# SCH_SpaceDrums_easyeda.net
KiCad netlist of a schematic drawn in EasyEDA
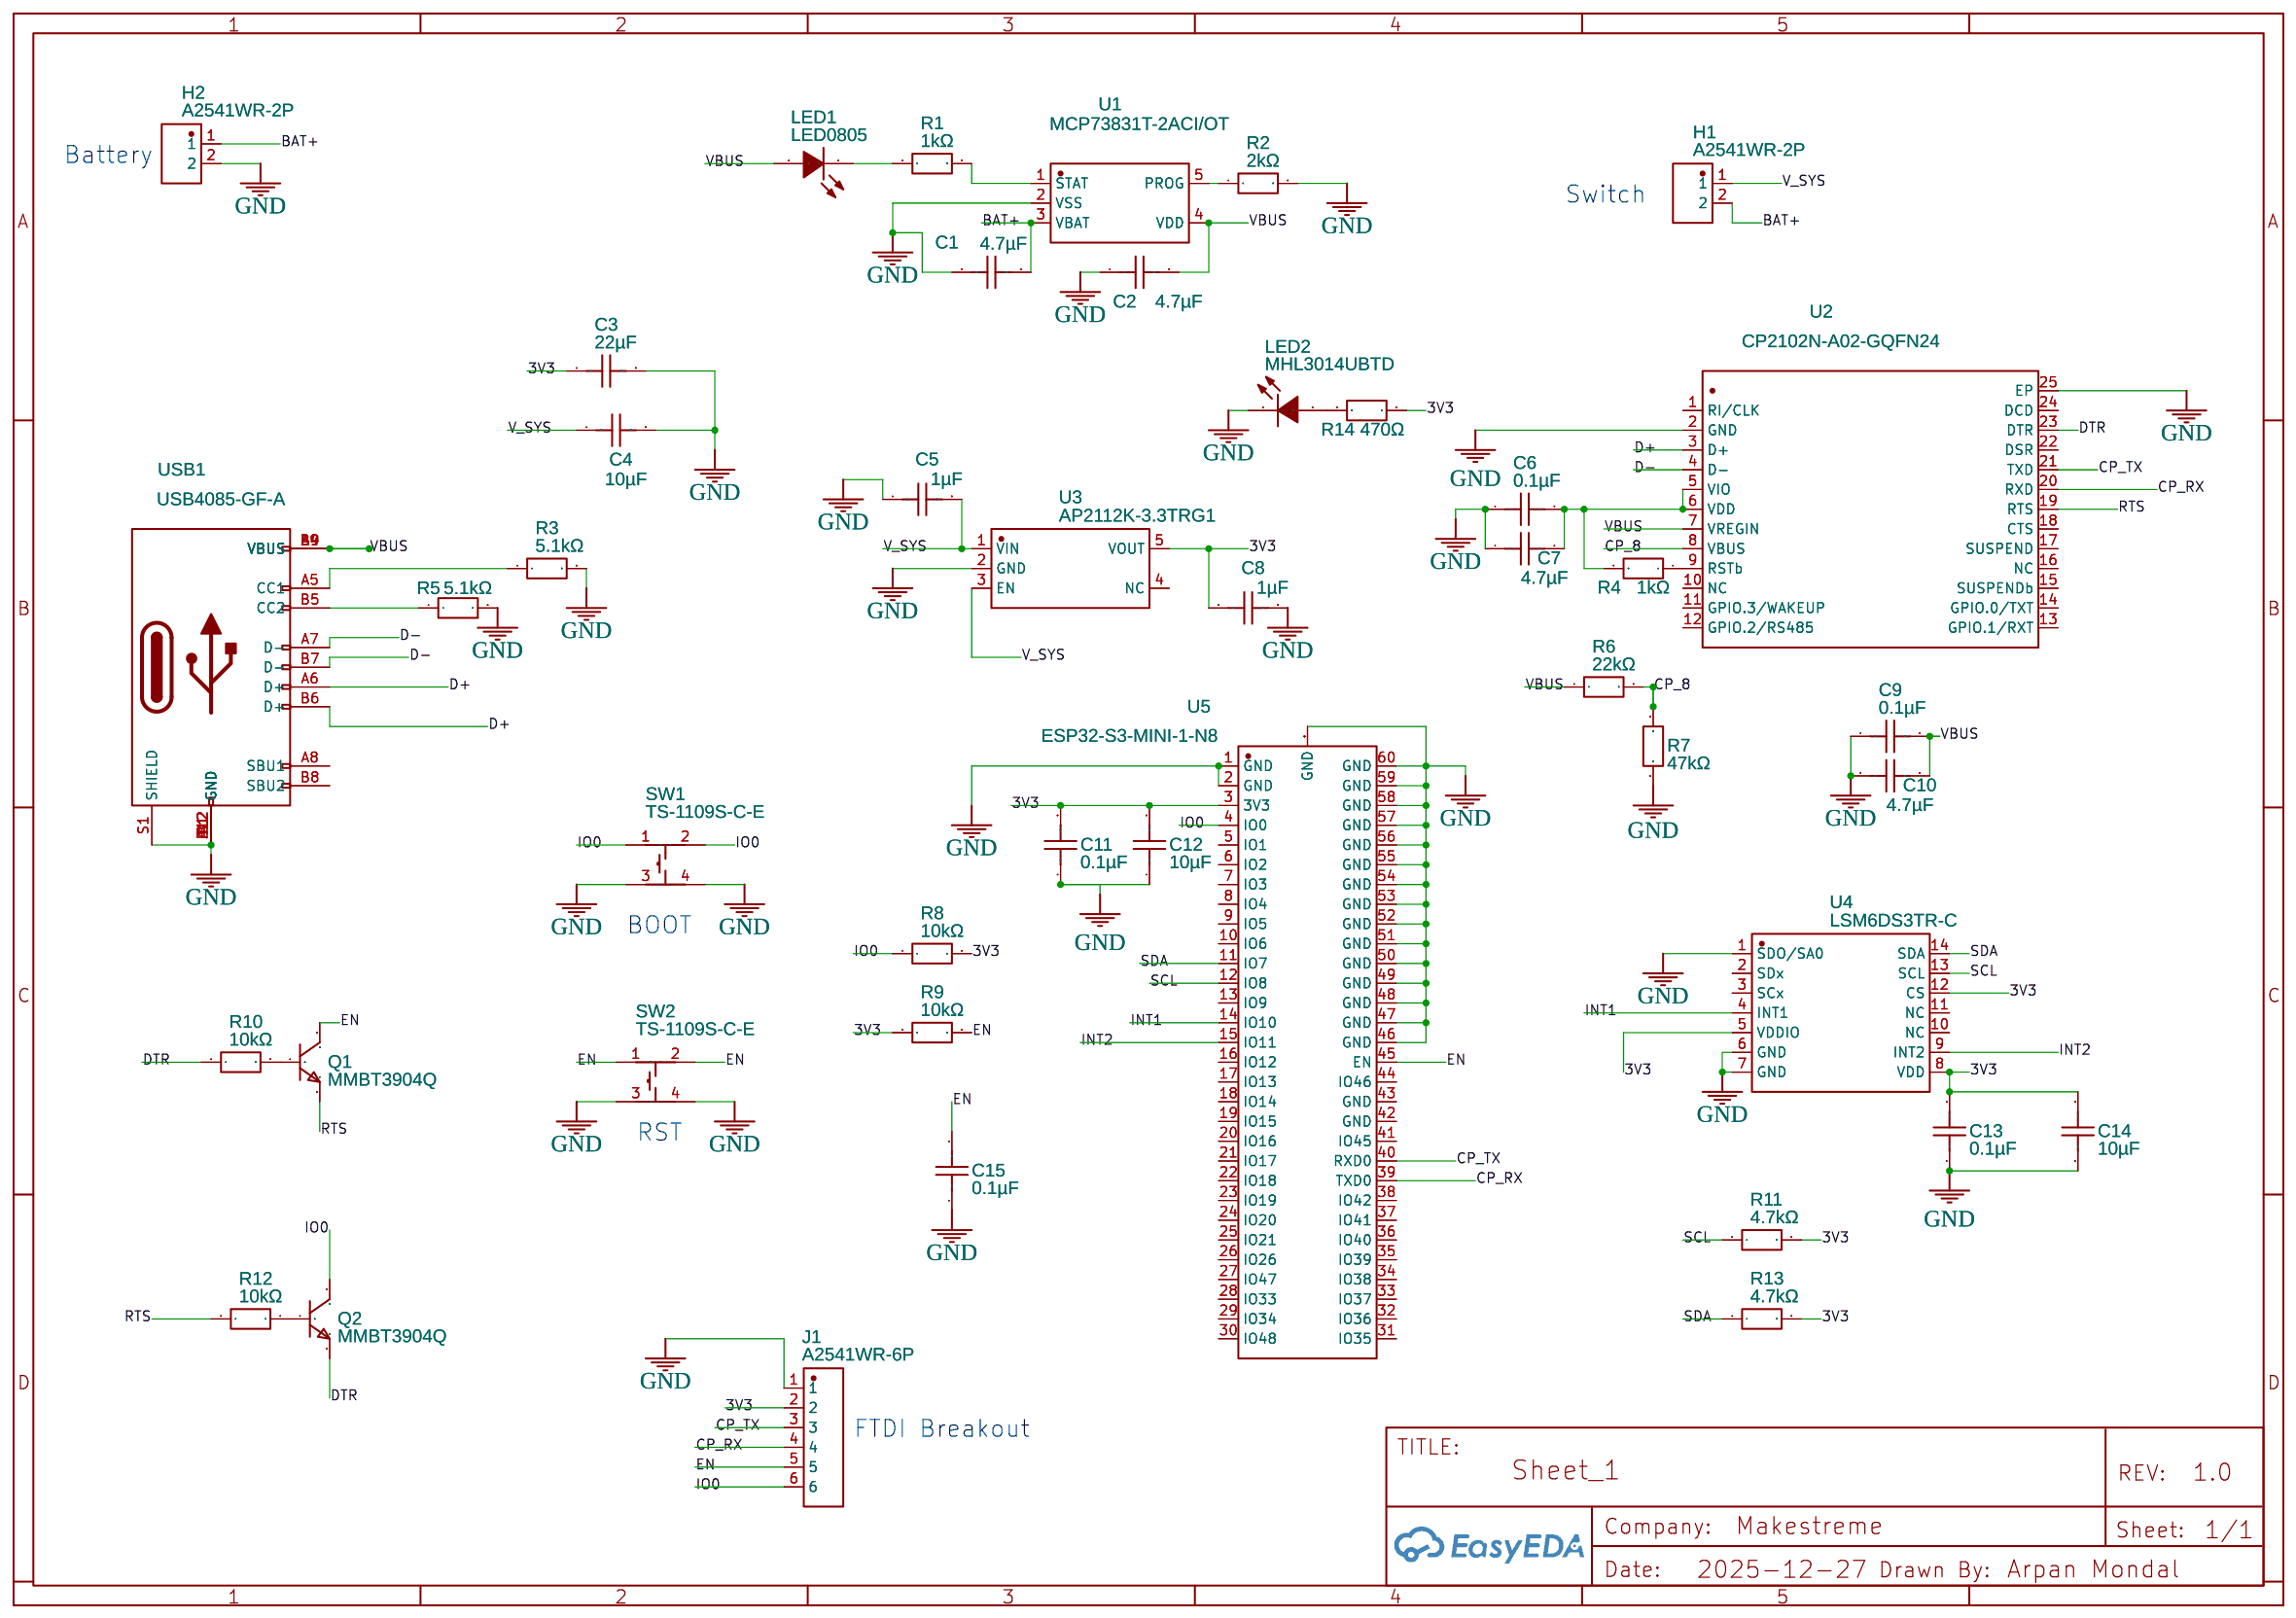
[diagram p0: schematic sheet]

(export (version "E")
  (design (tool "Eeschema 10.0.6"))
  (components
    (comp (ref "C1")
      (value "4.7µF")
      (fields
        (field (name "Manufacturer Part") "CC0805FRNPO0BN680")
        (field (name "Manufacturer") "YAGEO(国巨)")
      )
      (libsource (lib "") (part "CC0805FRNPO0BN680"))
    )
    (comp (ref "C2")
      (value "4.7µF")
      (fields
        (field (name "Manufacturer Part") "CC0805FRNPO0BN680")
        (field (name "Manufacturer") "YAGEO(国巨)")
      )
      (libsource (lib "") (part "CC0805FRNPO0BN680"))
    )
    (comp (ref "C3")
      (value "22µF")
      (fields
        (field (name "Manufacturer Part") "CC0805FRNPO0BN680")
        (field (name "Manufacturer") "YAGEO(国巨)")
      )
      (libsource (lib "") (part "CC0805FRNPO0BN680"))
    )
    (comp (ref "C4")
      (value "10µF")
      (fields
        (field (name "Manufacturer Part") "CC0805FRNPO0BN680")
        (field (name "Manufacturer") "YAGEO(国巨)")
      )
      (libsource (lib "") (part "CC0805FRNPO0BN680"))
    )
    (comp (ref "C5")
      (value "1µF")
      (fields
        (field (name "Manufacturer Part") "CC0805FRNPO0BN680")
        (field (name "Manufacturer") "YAGEO(国巨)")
      )
      (libsource (lib "") (part "CC0805FRNPO0BN680"))
    )
    (comp (ref "C6")
      (value "0.1µF")
      (fields
        (field (name "Manufacturer Part") "CC0805FRNPO0BN680")
        (field (name "Manufacturer") "YAGEO(国巨)")
      )
      (libsource (lib "") (part "CC0805FRNPO0BN680"))
    )
    (comp (ref "C7")
      (value "4.7µF")
      (fields
        (field (name "Manufacturer Part") "CC0805FRNPO0BN680")
        (field (name "Manufacturer") "YAGEO(国巨)")
      )
      (libsource (lib "") (part "CC0805FRNPO0BN680"))
    )
    (comp (ref "C8")
      (value "1µF")
      (fields
        (field (name "Manufacturer Part") "CC0805FRNPO0BN680")
        (field (name "Manufacturer") "YAGEO(国巨)")
      )
      (libsource (lib "") (part "CC0805FRNPO0BN680"))
    )
    (comp (ref "C9")
      (value "0.1µF")
      (fields
        (field (name "Manufacturer Part") "CC0805FRNPO0BN680")
        (field (name "Manufacturer") "YAGEO(国巨)")
      )
      (libsource (lib "") (part "CC0805FRNPO0BN680"))
    )
    (comp (ref "C10")
      (value "4.7µF")
      (fields
        (field (name "Manufacturer Part") "CC0805FRNPO0BN680")
        (field (name "Manufacturer") "YAGEO(国巨)")
      )
      (libsource (lib "") (part "CC0805FRNPO0BN680"))
    )
    (comp (ref "C11")
      (value "0.1µF")
      (fields
        (field (name "Manufacturer Part") "CC0805FRNPO0BN680")
        (field (name "Manufacturer") "YAGEO(国巨)")
      )
      (libsource (lib "") (part "CC0805FRNPO0BN680_1"))
    )
    (comp (ref "C12")
      (value "10µF")
      (fields
        (field (name "Manufacturer Part") "CC0805FRNPO0BN680")
        (field (name "Manufacturer") "YAGEO(国巨)")
      )
      (libsource (lib "") (part "CC0805FRNPO0BN680_1"))
    )
    (comp (ref "C13")
      (value "0.1µF")
      (fields
        (field (name "Manufacturer Part") "CC0805FRNPO0BN680")
        (field (name "Manufacturer") "YAGEO(国巨)")
      )
      (libsource (lib "") (part "CC0805FRNPO0BN680_1"))
    )
    (comp (ref "C14")
      (value "10µF")
      (fields
        (field (name "Manufacturer Part") "CC0805FRNPO0BN680")
        (field (name "Manufacturer") "YAGEO(国巨)")
      )
      (libsource (lib "") (part "CC0805FRNPO0BN680_1"))
    )
    (comp (ref "C15")
      (value "0.1µF")
      (fields
        (field (name "Manufacturer Part") "CC0805FRNPO0BN680")
        (field (name "Manufacturer") "YAGEO(国巨)")
      )
      (libsource (lib "") (part "CC0805FRNPO0BN680_1"))
    )
    (comp (ref "H1")
      (value "A2541WR-2P")
      (fields (field (name "Manufacturer") "CJT(长江连接器)"))
      (libsource (lib "") (part "A2541WR-2P"))
    )
    (comp (ref "H2")
      (value "A2541WR-2P")
      (fields (field (name "Manufacturer") "CJT(长江连接器)"))
      (libsource (lib "") (part "A2541WR-2P"))
    )
    (comp (ref "J1")
      (value "A2541WR-6P")
      (fields (field (name "Manufacturer") "CJT(长江连接器)"))
      (libsource (lib "") (part "A2541WR-6P"))
    )
    (comp (ref "LED1")
      (value "LED0805")
      (fields (field (name "Manufacturer Part") "led0805"))
      (libsource (lib "") (part "LED0805"))
    )
    (comp (ref "LED2")
      (value "MHL3014UBTD")
      (fields (field (name "Manufacturer") "MEIHUA(美华)"))
      (libsource (lib "") (part "MHL3014UBTD"))
    )
    (comp (ref "Q1")
      (value "MMBT3904Q")
      (fields (field (name "Manufacturer") "YANGJIE(扬杰)"))
      (libsource (lib "") (part "MMBT3904Q"))
    )
    (comp (ref "Q2")
      (value "MMBT3904Q")
      (fields (field (name "Manufacturer") "YANGJIE(扬杰)"))
      (libsource (lib "") (part "MMBT3904Q"))
    )
    (comp (ref "R1")
      (value "1kΩ")
      (fields (field (name "Manufacturer Part") "FRC0805F7873TS") (field (name "Manufacturer") "FOJAN(富捷)"))
      (libsource (lib "") (part "FRC0805F7873TS"))
    )
    (comp (ref "R2")
      (value "2kΩ")
      (fields (field (name "Manufacturer Part") "FRC0805F7873TS") (field (name "Manufacturer") "FOJAN(富捷)"))
      (libsource (lib "") (part "FRC0805F7873TS"))
    )
    (comp (ref "R3")
      (value "5.1kΩ")
      (fields (field (name "Manufacturer Part") "FRC0805F7873TS") (field (name "Manufacturer") "FOJAN(富捷)"))
      (libsource (lib "") (part "FRC0805F7873TS"))
    )
    (comp (ref "R4")
      (value "1kΩ")
      (fields (field (name "Manufacturer Part") "FRC0805F7873TS") (field (name "Manufacturer") "FOJAN(富捷)"))
      (libsource (lib "") (part "FRC0805F7873TS_1"))
    )
    (comp (ref "R5")
      (value "5.1kΩ")
      (fields (field (name "Manufacturer Part") "FRC0805F7873TS") (field (name "Manufacturer") "FOJAN(富捷)"))
      (libsource (lib "") (part "FRC0805F7873TS"))
    )
    (comp (ref "R6")
      (value "22kΩ")
      (fields (field (name "Manufacturer Part") "FRC0805F7873TS") (field (name "Manufacturer") "FOJAN(富捷)"))
      (libsource (lib "") (part "FRC0805F7873TS"))
    )
    (comp (ref "R7")
      (value "47kΩ")
      (fields (field (name "Manufacturer Part") "FRC0805F7873TS") (field (name "Manufacturer") "FOJAN(富捷)"))
      (libsource (lib "") (part "FRC0805F7873TS_2"))
    )
    (comp (ref "R8")
      (value "10kΩ")
      (fields (field (name "Manufacturer Part") "FRC0805F7873TS") (field (name "Manufacturer") "FOJAN(富捷)"))
      (libsource (lib "") (part "FRC0805F7873TS"))
    )
    (comp (ref "R9")
      (value "10kΩ")
      (fields (field (name "Manufacturer Part") "FRC0805F7873TS") (field (name "Manufacturer") "FOJAN(富捷)"))
      (libsource (lib "") (part "FRC0805F7873TS"))
    )
    (comp (ref "R10")
      (value "10kΩ")
      (fields (field (name "Manufacturer Part") "FRC0805F7873TS") (field (name "Manufacturer") "FOJAN(富捷)"))
      (libsource (lib "") (part "FRC0805F7873TS"))
    )
    (comp (ref "R11")
      (value "4.7kΩ")
      (fields (field (name "Manufacturer Part") "FRC0805F7873TS") (field (name "Manufacturer") "FOJAN(富捷)"))
      (libsource (lib "") (part "FRC0805F7873TS"))
    )
    (comp (ref "R12")
      (value "10kΩ")
      (fields (field (name "Manufacturer Part") "FRC0805F7873TS") (field (name "Manufacturer") "FOJAN(富捷)"))
      (libsource (lib "") (part "FRC0805F7873TS_1"))
    )
    (comp (ref "R13")
      (value "4.7kΩ")
      (fields (field (name "Manufacturer Part") "FRC0805F7873TS") (field (name "Manufacturer") "FOJAN(富捷)"))
      (libsource (lib "") (part "FRC0805F7873TS"))
    )
    (comp (ref "R14")
      (value "470Ω")
      (fields (field (name "Manufacturer Part") "FRC0805F7873TS") (field (name "Manufacturer") "FOJAN(富捷)"))
      (libsource (lib "") (part "FRC0805F7873TS_1"))
    )
    (comp (ref "SW1")
      (value "TS-1109S-C-E")
      (fields (field (name "Manufacturer") "XKB Connectivity(中国星坤)"))
      (libsource (lib "") (part "TS-1109S-C-E"))
    )
    (comp (ref "SW2")
      (value "TS-1109S-C-E")
      (fields (field (name "Manufacturer") "XKB Connectivity(中国星坤)"))
      (libsource (lib "") (part "TS-1109S-C-E"))
    )
    (comp (ref "U1")
      (value "MCP73831T-2ACI/OT")
      (fields (field (name "Manufacturer") "MICROCHIP(美国微芯)"))
      (libsource (lib "") (part "MCP73831T-2ACI/OT"))
    )
    (comp (ref "U2")
      (value "CP2102N-A02-GQFN24")
      (fields (field (name "Manufacturer") "SKYWORKS/SILICON LABS(芯科)"))
      (libsource (lib "") (part "CP2102N-A02-GQFN24"))
    )
    (comp (ref "U3")
      (value "AP2112K-3.3TRG1")
      (fields (field (name "Manufacturer") "DIODES(美台)"))
      (libsource (lib "") (part "AP2112K-3.3TRG1"))
    )
    (comp (ref "U4")
      (value "LSM6DS3TR-C")
      (fields (field (name "Manufacturer") "ST(意法半导体)"))
      (libsource (lib "") (part "LSM6DS3TR-C"))
    )
    (comp (ref "U5")
      (value "ESP32-S3-MINI-1-N8")
      (fields (field (name "Manufacturer") "ESPRESSIF(乐鑫)"))
      (libsource (lib "") (part "ESP32-S3-MINI-1-N8"))
    )
    (comp (ref "USB1") (value "USB4085-GF-A") (libsource (lib "") (part "USB4085-GF-A")))
  )
  (nets
    (net (code "1") (name "/3V3") (class "Default")
      (node (ref "C11") (pin "2") (pinfunction "2_2") (pintype "unspecified"))
      (node (ref "C12") (pin "2") (pinfunction "2_2") (pintype "unspecified"))
      (node (ref "C13") (pin "2") (pinfunction "2_2") (pintype "unspecified"))
      (node (ref "C14") (pin "2") (pinfunction "2_2") (pintype "unspecified"))
      (node (ref "C3") (pin "1") (pinfunction "1_1") (pintype "unspecified"))
      (node (ref "C8") (pin "1") (pinfunction "1_1") (pintype "unspecified"))
      (node (ref "J1") (pin "2") (pinfunction "2_2") (pintype "unspecified"))
      (node (ref "R11") (pin "2") (pinfunction "2_2") (pintype "unspecified"))
      (node (ref "R13") (pin "2") (pinfunction "2_2") (pintype "unspecified"))
      (node (ref "R14") (pin "1") (pinfunction "1_1") (pintype "unspecified"))
      (node (ref "R8") (pin "2") (pinfunction "2_2") (pintype "unspecified"))
      (node (ref "R9") (pin "1") (pinfunction "1_1") (pintype "unspecified"))
      (node (ref "U3") (pin "5") (pinfunction "VOUT_5") (pintype "unspecified"))
      (node (ref "U4") (pin "12") (pinfunction "CS_12") (pintype "unspecified"))
      (node (ref "U4") (pin "5") (pinfunction "VDDIO_5") (pintype "unspecified"))
      (node (ref "U4") (pin "8") (pinfunction "VDD_8") (pintype "unspecified"))
      (node (ref "U5") (pin "3") (pinfunction "3V3_3") (pintype "unspecified"))
    )
    (net (code "2") (name "/BAT+") (class "Default")
      (node (ref "C1") (pin "2") (pinfunction "2_2") (pintype "unspecified"))
      (node (ref "H1") (pin "2") (pinfunction "2_2") (pintype "unspecified"))
      (node (ref "H2") (pin "1") (pinfunction "1_1") (pintype "unspecified"))
      (node (ref "U1") (pin "3") (pinfunction "VBAT_3") (pintype "unspecified"))
    )
    (net (code "3") (name "/CP_8") (class "Default")
      (node (ref "R6") (pin "2") (pinfunction "2_2") (pintype "unspecified"))
      (node (ref "R7") (pin "2") (pinfunction "2_2") (pintype "unspecified"))
      (node (ref "U2") (pin "8") (pinfunction "VBUS_8") (pintype "unspecified"))
    )
    (net (code "4") (name "/CP_RX") (class "Default")
      (node (ref "J1") (pin "4") (pinfunction "4_4") (pintype "unspecified"))
      (node (ref "U2") (pin "20") (pinfunction "RXD_20") (pintype "unspecified"))
      (node (ref "U5") (pin "39") (pinfunction "TXD0_39") (pintype "unspecified"))
    )
    (net (code "5") (name "/CP_TX") (class "Default")
      (node (ref "J1") (pin "3") (pinfunction "3_3") (pintype "unspecified"))
      (node (ref "U2") (pin "21") (pinfunction "TXD_21") (pintype "unspecified"))
      (node (ref "U5") (pin "40") (pinfunction "RXD0_40") (pintype "unspecified"))
    )
    (net (code "6") (name "/D+") (class "Default")
      (node (ref "U2") (pin "3") (pinfunction "D+_3") (pintype "unspecified"))
      (node (ref "USB1") (pin "A6") (pinfunction "D+_A6") (pintype "bidirectional"))
      (node (ref "USB1") (pin "B6") (pinfunction "D+_B6") (pintype "bidirectional"))
    )
    (net (code "7") (name "/D-") (class "Default")
      (node (ref "U2") (pin "4") (pinfunction "D-_4") (pintype "unspecified"))
      (node (ref "USB1") (pin "A7") (pinfunction "D-_A7") (pintype "bidirectional"))
      (node (ref "USB1") (pin "B7") (pinfunction "D-_B7") (pintype "bidirectional"))
    )
    (net (code "8") (name "/DTR") (class "Default")
      (node (ref "Q2") (pin "2") (pinfunction "E_2") (pintype "unspecified"))
      (node (ref "R10") (pin "1") (pinfunction "1_1") (pintype "unspecified"))
      (node (ref "U2") (pin "23") (pinfunction "DTR_23") (pintype "unspecified"))
    )
    (net (code "9") (name "/EN") (class "Default")
      (node (ref "C15") (pin "2") (pinfunction "2_2") (pintype "unspecified"))
      (node (ref "J1") (pin "5") (pinfunction "5_5") (pintype "unspecified"))
      (node (ref "Q1") (pin "3") (pinfunction "C_3") (pintype "unspecified"))
      (node (ref "R9") (pin "2") (pinfunction "2_2") (pintype "unspecified"))
      (node (ref "SW2") (pin "1") (pinfunction "1_1") (pintype "unspecified"))
      (node (ref "SW2") (pin "2") (pinfunction "2_2") (pintype "unspecified"))
      (node (ref "U5") (pin "45") (pinfunction "EN_45") (pintype "unspecified"))
    )
    (net (code "10") (name "/INT1") (class "Default")
      (node (ref "U4") (pin "4") (pinfunction "INT1_4") (pintype "unspecified"))
      (node (ref "U5") (pin "14") (pinfunction "IO10_14") (pintype "unspecified"))
    )
    (net (code "11") (name "/INT2") (class "Default")
      (node (ref "U4") (pin "9") (pinfunction "INT2_9") (pintype "unspecified"))
      (node (ref "U5") (pin "15") (pinfunction "IO11_15") (pintype "unspecified"))
    )
    (net (code "12") (name "/IO0") (class "Default")
      (node (ref "J1") (pin "6") (pinfunction "6_6") (pintype "unspecified"))
      (node (ref "Q2") (pin "3") (pinfunction "C_3") (pintype "unspecified"))
      (node (ref "R8") (pin "1") (pinfunction "1_1") (pintype "unspecified"))
      (node (ref "SW1") (pin "1") (pinfunction "1_1") (pintype "unspecified"))
      (node (ref "SW1") (pin "2") (pinfunction "2_2") (pintype "unspecified"))
      (node (ref "U5") (pin "4") (pinfunction "IO0_4") (pintype "unspecified"))
    )
    (net (code "13") (name "/RTS") (class "Default")
      (node (ref "Q1") (pin "2") (pinfunction "E_2") (pintype "unspecified"))
      (node (ref "R12") (pin "2") (pinfunction "2_2") (pintype "unspecified"))
      (node (ref "U2") (pin "19") (pinfunction "RTS_19") (pintype "unspecified"))
    )
    (net (code "14") (name "/SCL") (class "Default")
      (node (ref "R11") (pin "1") (pinfunction "1_1") (pintype "unspecified"))
      (node (ref "U4") (pin "13") (pinfunction "SCL_13") (pintype "unspecified"))
      (node (ref "U5") (pin "12") (pinfunction "IO8_12") (pintype "unspecified"))
    )
    (net (code "15") (name "/SDA") (class "Default")
      (node (ref "R13") (pin "1") (pinfunction "1_1") (pintype "unspecified"))
      (node (ref "U4") (pin "14") (pinfunction "SDA_14") (pintype "unspecified"))
      (node (ref "U5") (pin "11") (pinfunction "IO7_11") (pintype "unspecified"))
    )
    (net (code "16") (name "/VBUS") (class "Default")
      (node (ref "C10") (pin "2") (pinfunction "2_2") (pintype "unspecified"))
      (node (ref "C2") (pin "2") (pinfunction "2_2") (pintype "unspecified"))
      (node (ref "C9") (pin "2") (pinfunction "2_2") (pintype "unspecified"))
      (node (ref "LED1") (pin "2") (pinfunction "+_2") (pintype "unspecified"))
      (node (ref "R6") (pin "1") (pinfunction "1_1") (pintype "unspecified"))
      (node (ref "U1") (pin "4") (pinfunction "VDD_4") (pintype "unspecified"))
      (node (ref "U2") (pin "7") (pinfunction "VREGIN_7") (pintype "unspecified"))
      (node (ref "USB1") (pin "A4") (pinfunction "VBUS_A4") (pintype "bidirectional"))
      (node (ref "USB1") (pin "A9") (pinfunction "VBUS_A9") (pintype "unspecified"))
      (node (ref "USB1") (pin "B4") (pinfunction "VBUS_B4") (pintype "unspecified"))
      (node (ref "USB1") (pin "B9") (pinfunction "VBUS_B9") (pintype "unspecified"))
    )
    (net (code "17") (name "/V_SYS") (class "Default")
      (node (ref "C4") (pin "1") (pinfunction "1_1") (pintype "unspecified"))
      (node (ref "C5") (pin "2") (pinfunction "2_2") (pintype "unspecified"))
      (node (ref "H1") (pin "1") (pinfunction "1_1") (pintype "unspecified"))
      (node (ref "U3") (pin "1") (pinfunction "VIN_1") (pintype "unspecified"))
      (node (ref "U3") (pin "3") (pinfunction "EN_3") (pintype "unspecified"))
    )
    (net (code "18") (name "GND") (class "Default")
      (node (ref "C1") (pin "1") (pinfunction "1_1") (pintype "unspecified"))
      (node (ref "C10") (pin "1") (pinfunction "1_1") (pintype "unspecified"))
      (node (ref "C11") (pin "1") (pinfunction "1_1") (pintype "unspecified"))
      (node (ref "C12") (pin "1") (pinfunction "1_1") (pintype "unspecified"))
      (node (ref "C13") (pin "1") (pinfunction "1_1") (pintype "unspecified"))
      (node (ref "C14") (pin "1") (pinfunction "1_1") (pintype "unspecified"))
      (node (ref "C15") (pin "1") (pinfunction "1_1") (pintype "unspecified"))
      (node (ref "C2") (pin "1") (pinfunction "1_1") (pintype "unspecified"))
      (node (ref "C3") (pin "2") (pinfunction "2_2") (pintype "unspecified"))
      (node (ref "C4") (pin "2") (pinfunction "2_2") (pintype "unspecified"))
      (node (ref "C5") (pin "1") (pinfunction "1_1") (pintype "unspecified"))
      (node (ref "C6") (pin "1") (pinfunction "1_1") (pintype "unspecified"))
      (node (ref "C7") (pin "1") (pinfunction "1_1") (pintype "unspecified"))
      (node (ref "C8") (pin "2") (pinfunction "2_2") (pintype "unspecified"))
      (node (ref "C9") (pin "1") (pinfunction "1_1") (pintype "unspecified"))
      (node (ref "H2") (pin "2") (pinfunction "2_2") (pintype "unspecified"))
      (node (ref "J1") (pin "1") (pinfunction "1_1") (pintype "unspecified"))
      (node (ref "LED2") (pin "1") (pinfunction "-_1") (pintype "unspecified"))
      (node (ref "R2") (pin "2") (pinfunction "2_2") (pintype "unspecified"))
      (node (ref "R3") (pin "2") (pinfunction "2_2") (pintype "unspecified"))
      (node (ref "R5") (pin "2") (pinfunction "2_2") (pintype "unspecified"))
      (node (ref "R7") (pin "1") (pinfunction "1_1") (pintype "unspecified"))
      (node (ref "SW1") (pin "3") (pinfunction "3_3") (pintype "unspecified"))
      (node (ref "SW1") (pin "4") (pinfunction "4_4") (pintype "unspecified"))
      (node (ref "SW2") (pin "3") (pinfunction "3_3") (pintype "unspecified"))
      (node (ref "SW2") (pin "4") (pinfunction "4_4") (pintype "unspecified"))
      (node (ref "U1") (pin "2") (pinfunction "VSS_2") (pintype "unspecified"))
      (node (ref "U2") (pin "2") (pinfunction "GND_2") (pintype "unspecified"))
      (node (ref "U2") (pin "25") (pinfunction "EP_25") (pintype "unspecified"))
      (node (ref "U3") (pin "2") (pinfunction "GND_2") (pintype "unspecified"))
      (node (ref "U4") (pin "1") (pinfunction "SDO/SA0_1") (pintype "unspecified"))
      (node (ref "U4") (pin "6") (pinfunction "GND_6") (pintype "unspecified"))
      (node (ref "U4") (pin "7") (pinfunction "GND_7") (pintype "unspecified"))
      (node (ref "U5") (pin "1") (pinfunction "GND_1") (pintype "unspecified"))
      (node (ref "U5") (pin "2") (pinfunction "GND_2") (pintype "unspecified"))
      (node (ref "U5") (pin "46") (pinfunction "GND_46") (pintype "unspecified"))
      (node (ref "U5") (pin "47") (pinfunction "GND_47") (pintype "unspecified"))
      (node (ref "U5") (pin "48") (pinfunction "GND_48") (pintype "unspecified"))
      (node (ref "U5") (pin "49") (pinfunction "GND_49") (pintype "unspecified"))
      (node (ref "U5") (pin "50") (pinfunction "GND_50") (pintype "unspecified"))
      (node (ref "U5") (pin "51") (pinfunction "GND_51") (pintype "unspecified"))
      (node (ref "U5") (pin "52") (pinfunction "GND_52") (pintype "unspecified"))
      (node (ref "U5") (pin "53") (pinfunction "GND_53") (pintype "unspecified"))
      (node (ref "U5") (pin "54") (pinfunction "GND_54") (pintype "unspecified"))
      (node (ref "U5") (pin "55") (pinfunction "GND_55") (pintype "unspecified"))
      (node (ref "U5") (pin "56") (pinfunction "GND_56") (pintype "unspecified"))
      (node (ref "U5") (pin "57") (pinfunction "GND_57") (pintype "unspecified"))
      (node (ref "U5") (pin "58") (pinfunction "GND_58") (pintype "unspecified"))
      (node (ref "U5") (pin "59") (pinfunction "GND_59") (pintype "unspecified"))
      (node (ref "U5") (pin "60") (pinfunction "GND_60") (pintype "unspecified"))
      (node (ref "U5") (pin "GND") (pinfunction "GND_GND") (pintype "unspecified"))
      (node (ref "USB1") (pin "A1") (pinfunction "GND_A1") (pintype "bidirectional"))
      (node (ref "USB1") (pin "A12") (pinfunction "GND_A12") (pintype "unspecified"))
      (node (ref "USB1") (pin "B1") (pinfunction "GND_B1") (pintype "unspecified"))
      (node (ref "USB1") (pin "B12") (pinfunction "GND_B12") (pintype "unspecified"))
      (node (ref "USB1") (pin "S1") (pinfunction "SHIELD_S1") (pintype "unspecified"))
    )
    (net (code "19") (name "Net-(LED1--)") (class "Default")
      (node (ref "LED1") (pin "1") (pinfunction "-_1") (pintype "unspecified"))
      (node (ref "R1") (pin "1") (pinfunction "1_1") (pintype "unspecified"))
    )
    (net (code "20") (name "Net-(LED2-+)") (class "Default")
      (node (ref "LED2") (pin "2") (pinfunction "+_2") (pintype "unspecified"))
      (node (ref "R14") (pin "2") (pinfunction "2_2") (pintype "unspecified"))
    )
    (net (code "21") (name "Net-(Q1-B)") (class "Default")
      (node (ref "Q1") (pin "1") (pinfunction "B_1") (pintype "unspecified"))
      (node (ref "R10") (pin "2") (pinfunction "2_2") (pintype "unspecified"))
    )
    (net (code "22") (name "Net-(Q2-B)") (class "Default")
      (node (ref "Q2") (pin "1") (pinfunction "B_1") (pintype "unspecified"))
      (node (ref "R12") (pin "1") (pinfunction "1_1") (pintype "unspecified"))
    )
    (net (code "23") (name "Net-(U1-PROG)") (class "Default")
      (node (ref "R2") (pin "1") (pinfunction "1_1") (pintype "unspecified"))
      (node (ref "U1") (pin "5") (pinfunction "PROG_5") (pintype "unspecified"))
    )
    (net (code "24") (name "Net-(U1-STAT)") (class "Default")
      (node (ref "R1") (pin "2") (pinfunction "2_2") (pintype "unspecified"))
      (node (ref "U1") (pin "1") (pinfunction "STAT_1") (pintype "unspecified"))
    )
    (net (code "25") (name "Net-(U2-RSTb)") (class "Default")
      (node (ref "R4") (pin "1") (pinfunction "1_1") (pintype "unspecified"))
      (node (ref "U2") (pin "9") (pinfunction "RSTb_9") (pintype "unspecified"))
    )
    (net (code "26") (name "Net-(U2-VDD)") (class "Default")
      (node (ref "C6") (pin "2") (pinfunction "2_2") (pintype "unspecified"))
      (node (ref "C7") (pin "2") (pinfunction "2_2") (pintype "unspecified"))
      (node (ref "R4") (pin "2") (pinfunction "2_2") (pintype "unspecified"))
      (node (ref "U2") (pin "5") (pinfunction "VIO_5") (pintype "unspecified"))
      (node (ref "U2") (pin "6") (pinfunction "VDD_6") (pintype "unspecified"))
    )
    (net (code "27") (name "Net-(USB1-CC1)") (class "Default")
      (node (ref "R3") (pin "1") (pinfunction "1_1") (pintype "unspecified"))
      (node (ref "USB1") (pin "A5") (pinfunction "CC1_A5") (pintype "bidirectional"))
    )
    (net (code "28") (name "Net-(USB1-CC2)") (class "Default")
      (node (ref "R5") (pin "1") (pinfunction "1_1") (pintype "unspecified"))
      (node (ref "USB1") (pin "B5") (pinfunction "CC2_B5") (pintype "bidirectional"))
    )
    (net (code "29") (name "unconnected-(U2-CTS-Pad18)") (class "Default")
      (node (ref "U2") (pin "18") (pinfunction "CTS_18") (pintype "unspecified"))
    )
    (net (code "30") (name "unconnected-(U2-DCD-Pad24)") (class "Default")
      (node (ref "U2") (pin "24") (pinfunction "DCD_24") (pintype "unspecified"))
    )
    (net (code "31") (name "unconnected-(U2-DSR-Pad22)") (class "Default")
      (node (ref "U2") (pin "22") (pinfunction "DSR_22") (pintype "unspecified"))
    )
    (net (code "32") (name "unconnected-(U2-GPIO.0{slash}TXT-Pad14)") (class "Default")
      (node (ref "U2") (pin "14") (pinfunction "GPIO.0/TXT_14") (pintype "unspecified"))
    )
    (net (code "33") (name "unconnected-(U2-GPIO.1{slash}RXT-Pad13)") (class "Default")
      (node (ref "U2") (pin "13") (pinfunction "GPIO.1/RXT_13") (pintype "unspecified"))
    )
    (net (code "34") (name "unconnected-(U2-GPIO.2{slash}RS485-Pad12)") (class "Default")
      (node (ref "U2") (pin "12") (pinfunction "GPIO.2/RS485_12") (pintype "unspecified"))
    )
    (net (code "35") (name "unconnected-(U2-GPIO.3{slash}WAKEUP-Pad11)") (class "Default")
      (node (ref "U2") (pin "11") (pinfunction "GPIO.3/WAKEUP_11") (pintype "unspecified"))
    )
    (net (code "36") (name "unconnected-(U2-NC-Pad10)") (class "Default")
      (node (ref "U2") (pin "10") (pinfunction "NC_10") (pintype "unspecified"))
    )
    (net (code "37") (name "unconnected-(U2-NC-Pad16)") (class "Default")
      (node (ref "U2") (pin "16") (pinfunction "NC_16") (pintype "unspecified"))
    )
    (net (code "38") (name "unconnected-(U2-RI{slash}CLK-Pad1)") (class "Default")
      (node (ref "U2") (pin "1") (pinfunction "RI/CLK_1") (pintype "unspecified"))
    )
    (net (code "39") (name "unconnected-(U2-SUSPEND-Pad17)") (class "Default")
      (node (ref "U2") (pin "17") (pinfunction "SUSPEND_17") (pintype "unspecified"))
    )
    (net (code "40") (name "unconnected-(U2-SUSPENDb-Pad15)") (class "Default")
      (node (ref "U2") (pin "15") (pinfunction "SUSPENDb_15") (pintype "unspecified"))
    )
    (net (code "41") (name "unconnected-(U3-NC-Pad4)") (class "Default")
      (node (ref "U3") (pin "4") (pinfunction "NC_4") (pintype "unspecified"))
    )
    (net (code "42") (name "unconnected-(U4-NC-Pad10)") (class "Default")
      (node (ref "U4") (pin "10") (pinfunction "NC_10") (pintype "unspecified"))
    )
    (net (code "43") (name "unconnected-(U4-NC-Pad11)") (class "Default")
      (node (ref "U4") (pin "11") (pinfunction "NC_11") (pintype "unspecified"))
    )
    (net (code "44") (name "unconnected-(U4-SCx-Pad3)") (class "Default")
      (node (ref "U4") (pin "3") (pinfunction "SCx_3") (pintype "unspecified"))
    )
    (net (code "45") (name "unconnected-(U4-SDx-Pad2)") (class "Default")
      (node (ref "U4") (pin "2") (pinfunction "SDx_2") (pintype "unspecified"))
    )
    (net (code "46") (name "unconnected-(U5-GND-Pad42)") (class "Default")
      (node (ref "U5") (pin "42") (pinfunction "GND_42") (pintype "unspecified"))
    )
    (net (code "47") (name "unconnected-(U5-GND-Pad43)") (class "Default")
      (node (ref "U5") (pin "43") (pinfunction "GND_43") (pintype "unspecified"))
    )
    (net (code "48") (name "unconnected-(U5-IO1-Pad5)") (class "Default")
      (node (ref "U5") (pin "5") (pinfunction "IO1_5") (pintype "unspecified"))
    )
    (net (code "49") (name "unconnected-(U5-IO2-Pad6)") (class "Default")
      (node (ref "U5") (pin "6") (pinfunction "IO2_6") (pintype "unspecified"))
    )
    (net (code "50") (name "unconnected-(U5-IO3-Pad7)") (class "Default")
      (node (ref "U5") (pin "7") (pinfunction "IO3_7") (pintype "unspecified"))
    )
    (net (code "51") (name "unconnected-(U5-IO4-Pad8)") (class "Default")
      (node (ref "U5") (pin "8") (pinfunction "IO4_8") (pintype "unspecified"))
    )
    (net (code "52") (name "unconnected-(U5-IO5-Pad9)") (class "Default")
      (node (ref "U5") (pin "9") (pinfunction "IO5_9") (pintype "unspecified"))
    )
    (net (code "53") (name "unconnected-(U5-IO6-Pad10)") (class "Default")
      (node (ref "U5") (pin "10") (pinfunction "IO6_10") (pintype "unspecified"))
    )
    (net (code "54") (name "unconnected-(U5-IO9-Pad13)") (class "Default")
      (node (ref "U5") (pin "13") (pinfunction "IO9_13") (pintype "unspecified"))
    )
    (net (code "55") (name "unconnected-(U5-IO12-Pad16)") (class "Default")
      (node (ref "U5") (pin "16") (pinfunction "IO12_16") (pintype "unspecified"))
    )
    (net (code "56") (name "unconnected-(U5-IO13-Pad17)") (class "Default")
      (node (ref "U5") (pin "17") (pinfunction "IO13_17") (pintype "unspecified"))
    )
    (net (code "57") (name "unconnected-(U5-IO14-Pad18)") (class "Default")
      (node (ref "U5") (pin "18") (pinfunction "IO14_18") (pintype "unspecified"))
    )
    (net (code "58") (name "unconnected-(U5-IO15-Pad19)") (class "Default")
      (node (ref "U5") (pin "19") (pinfunction "IO15_19") (pintype "unspecified"))
    )
    (net (code "59") (name "unconnected-(U5-IO16-Pad20)") (class "Default")
      (node (ref "U5") (pin "20") (pinfunction "IO16_20") (pintype "unspecified"))
    )
    (net (code "60") (name "unconnected-(U5-IO17-Pad21)") (class "Default")
      (node (ref "U5") (pin "21") (pinfunction "IO17_21") (pintype "unspecified"))
    )
    (net (code "61") (name "unconnected-(U5-IO18-Pad22)") (class "Default")
      (node (ref "U5") (pin "22") (pinfunction "IO18_22") (pintype "unspecified"))
    )
    (net (code "62") (name "unconnected-(U5-IO19-Pad23)") (class "Default")
      (node (ref "U5") (pin "23") (pinfunction "IO19_23") (pintype "unspecified"))
    )
    (net (code "63") (name "unconnected-(U5-IO20-Pad24)") (class "Default")
      (node (ref "U5") (pin "24") (pinfunction "IO20_24") (pintype "unspecified"))
    )
    (net (code "64") (name "unconnected-(U5-IO21-Pad25)") (class "Default")
      (node (ref "U5") (pin "25") (pinfunction "IO21_25") (pintype "unspecified"))
    )
    (net (code "65") (name "unconnected-(U5-IO26-Pad26)") (class "Default")
      (node (ref "U5") (pin "26") (pinfunction "IO26_26") (pintype "unspecified"))
    )
    (net (code "66") (name "unconnected-(U5-IO33-Pad28)") (class "Default")
      (node (ref "U5") (pin "28") (pinfunction "IO33_28") (pintype "unspecified"))
    )
    (net (code "67") (name "unconnected-(U5-IO34-Pad29)") (class "Default")
      (node (ref "U5") (pin "29") (pinfunction "IO34_29") (pintype "unspecified"))
    )
    (net (code "68") (name "unconnected-(U5-IO35-Pad31)") (class "Default")
      (node (ref "U5") (pin "31") (pinfunction "IO35_31") (pintype "unspecified"))
    )
    (net (code "69") (name "unconnected-(U5-IO36-Pad32)") (class "Default")
      (node (ref "U5") (pin "32") (pinfunction "IO36_32") (pintype "unspecified"))
    )
    (net (code "70") (name "unconnected-(U5-IO37-Pad33)") (class "Default")
      (node (ref "U5") (pin "33") (pinfunction "IO37_33") (pintype "unspecified"))
    )
    (net (code "71") (name "unconnected-(U5-IO38-Pad34)") (class "Default")
      (node (ref "U5") (pin "34") (pinfunction "IO38_34") (pintype "unspecified"))
    )
    (net (code "72") (name "unconnected-(U5-IO39-Pad35)") (class "Default")
      (node (ref "U5") (pin "35") (pinfunction "IO39_35") (pintype "unspecified"))
    )
    (net (code "73") (name "unconnected-(U5-IO40-Pad36)") (class "Default")
      (node (ref "U5") (pin "36") (pinfunction "IO40_36") (pintype "unspecified"))
    )
    (net (code "74") (name "unconnected-(U5-IO41-Pad37)") (class "Default")
      (node (ref "U5") (pin "37") (pinfunction "IO41_37") (pintype "unspecified"))
    )
    (net (code "75") (name "unconnected-(U5-IO42-Pad38)") (class "Default")
      (node (ref "U5") (pin "38") (pinfunction "IO42_38") (pintype "unspecified"))
    )
    (net (code "76") (name "unconnected-(U5-IO45-Pad41)") (class "Default")
      (node (ref "U5") (pin "41") (pinfunction "IO45_41") (pintype "unspecified"))
    )
    (net (code "77") (name "unconnected-(U5-IO46-Pad44)") (class "Default")
      (node (ref "U5") (pin "44") (pinfunction "IO46_44") (pintype "unspecified"))
    )
    (net (code "78") (name "unconnected-(U5-IO47-Pad27)") (class "Default")
      (node (ref "U5") (pin "27") (pinfunction "IO47_27") (pintype "unspecified"))
    )
    (net (code "79") (name "unconnected-(U5-IO48-Pad30)") (class "Default")
      (node (ref "U5") (pin "30") (pinfunction "IO48_30") (pintype "unspecified"))
    )
    (net (code "80") (name "unconnected-(USB1-SBU1-PadA8)") (class "Default")
      (node (ref "USB1") (pin "A8") (pinfunction "SBU1_A8") (pintype "bidirectional"))
    )
    (net (code "81") (name "unconnected-(USB1-SBU2-PadB8)") (class "Default")
      (node (ref "USB1") (pin "B8") (pinfunction "SBU2_B8") (pintype "bidirectional"))
    )
  )
)
